# DVCA_v1_3.net
KiCad netlist of a schematic drawn in EAGLE
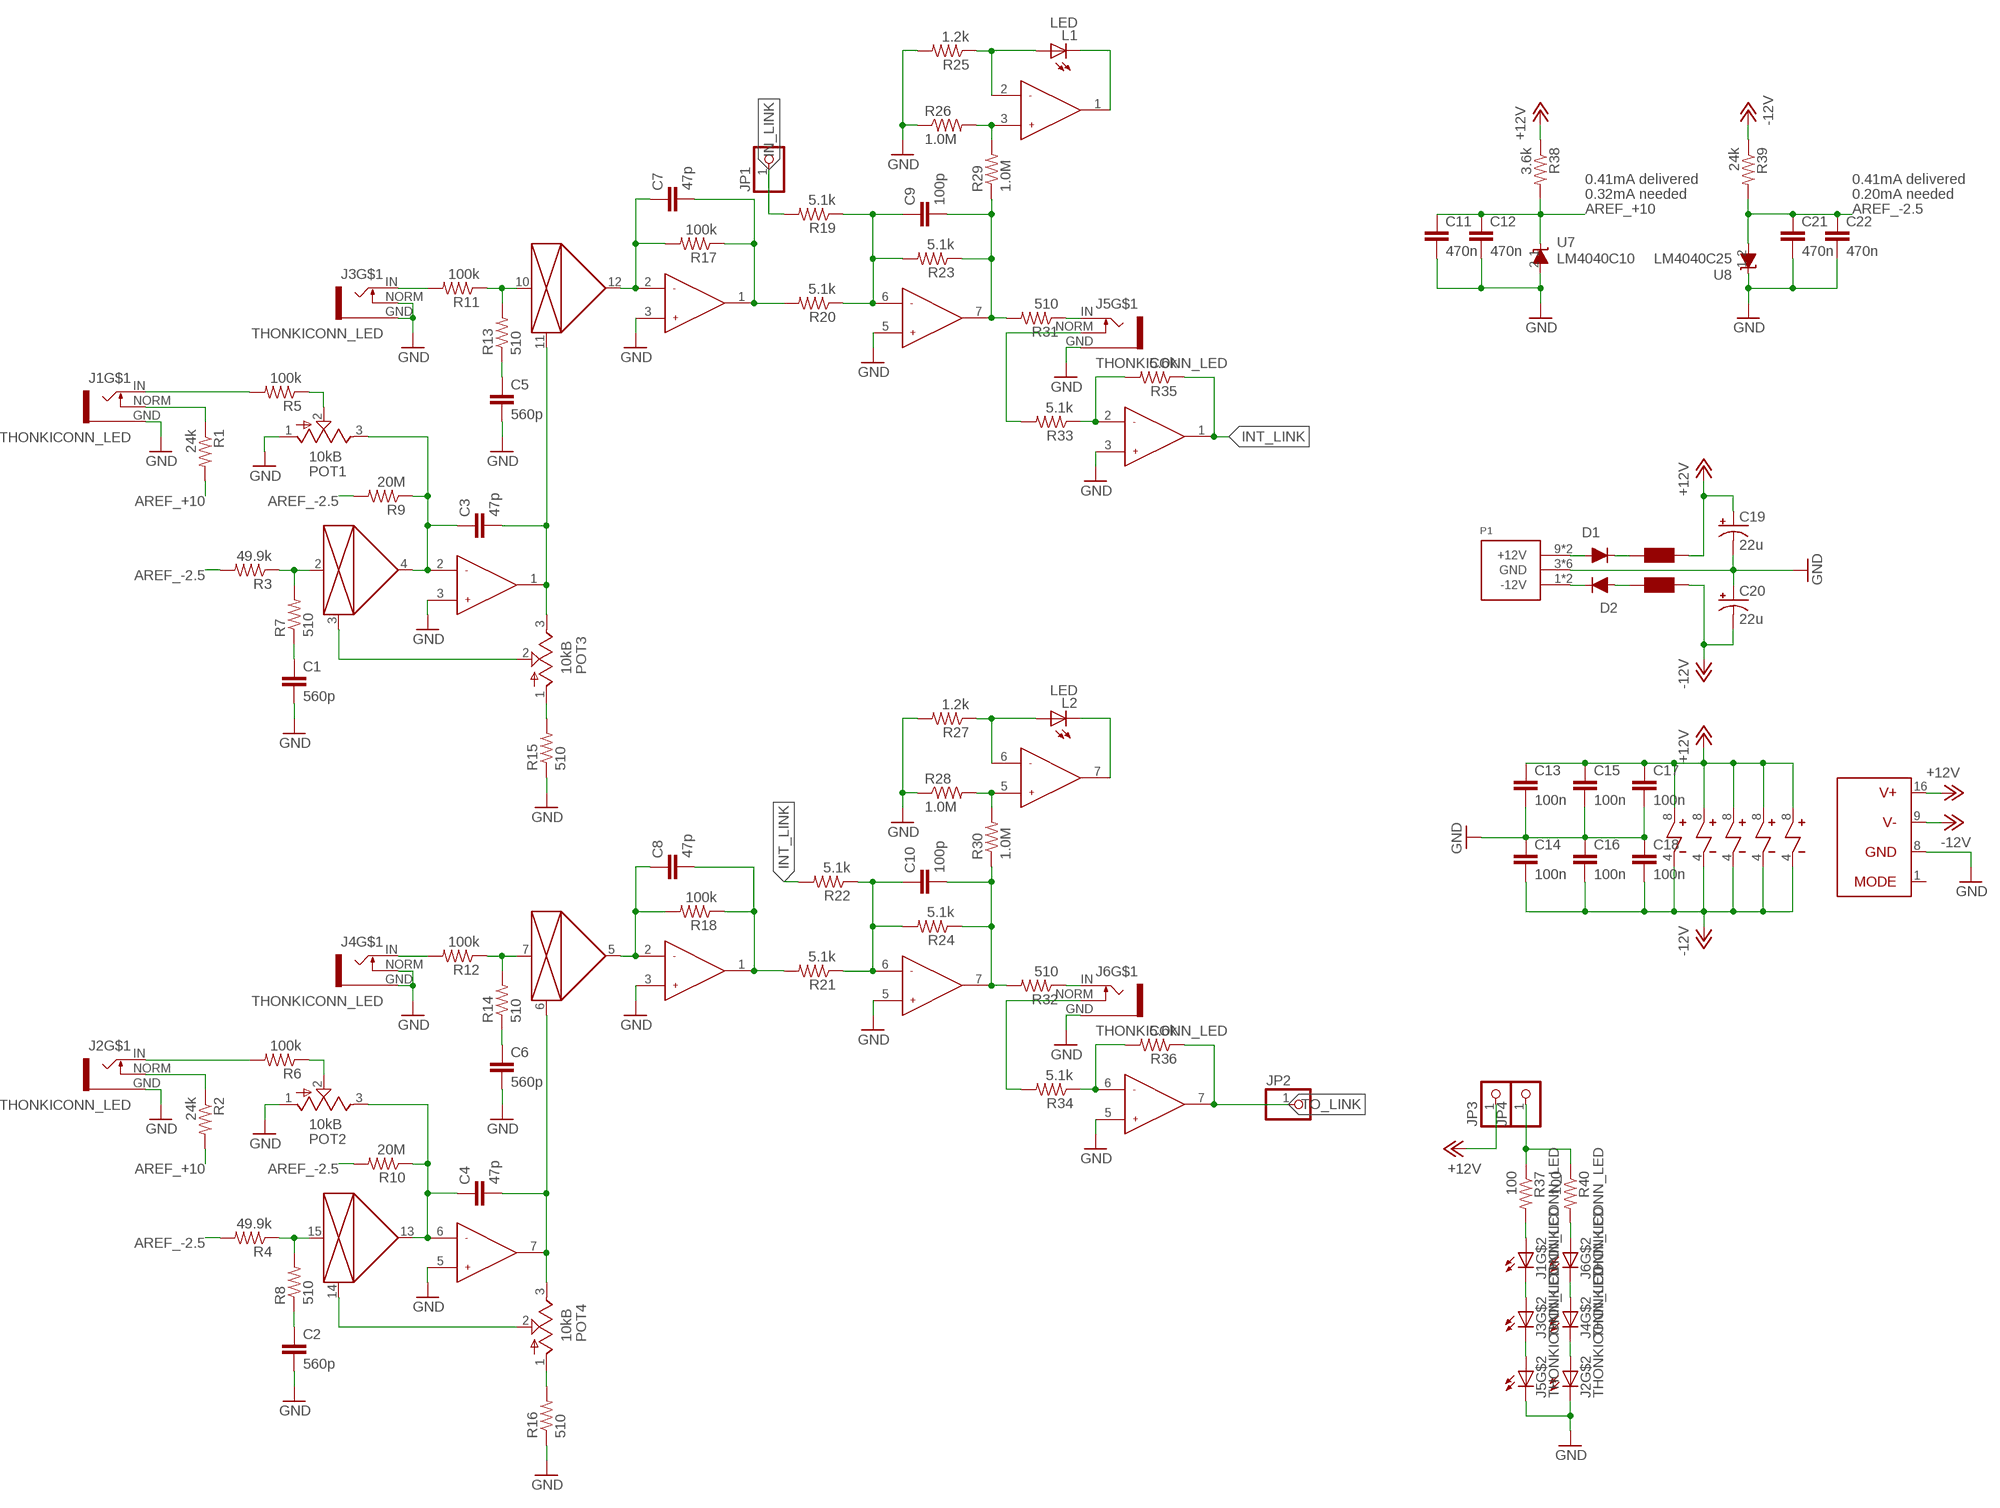
[diagram p0: schematic, sheet 1]

(export (version "E")
  (design (tool "Eeschema 10.0.6"))
  (components
    (comp (ref "C1")
      (value "560p")
      (footprint "eagle-import:RESISTOR_0603")
      (libsource (lib "eagle-import") (part "CAPACITOR"))
    )
    (comp (ref "C2")
      (value "560p")
      (footprint "eagle-import:RESISTOR_0603")
      (libsource (lib "eagle-import") (part "CAPACITOR"))
    )
    (comp (ref "C3")
      (value "47p")
      (footprint "eagle-import:RESISTOR_0603")
      (libsource (lib "eagle-import") (part "CAPACITOR"))
    )
    (comp (ref "C4")
      (value "47p")
      (footprint "eagle-import:RESISTOR_0603")
      (libsource (lib "eagle-import") (part "CAPACITOR"))
    )
    (comp (ref "C5")
      (value "560p")
      (footprint "eagle-import:RESISTOR_0603")
      (libsource (lib "eagle-import") (part "CAPACITOR"))
    )
    (comp (ref "C6")
      (value "560p")
      (footprint "eagle-import:RESISTOR_0603")
      (libsource (lib "eagle-import") (part "CAPACITOR"))
    )
    (comp (ref "C7")
      (value "47p")
      (footprint "eagle-import:RESISTOR_0603")
      (libsource (lib "eagle-import") (part "CAPACITOR"))
    )
    (comp (ref "C8")
      (value "47p")
      (footprint "eagle-import:RESISTOR_0603")
      (libsource (lib "eagle-import") (part "CAPACITOR"))
    )
    (comp (ref "C9")
      (value "100p")
      (footprint "eagle-import:RESISTOR_0603")
      (libsource (lib "eagle-import") (part "CAPACITOR"))
    )
    (comp (ref "C10")
      (value "100p")
      (footprint "eagle-import:RESISTOR_0603")
      (libsource (lib "eagle-import") (part "CAPACITOR"))
    )
    (comp (ref "C11")
      (value "470n")
      (footprint "eagle-import:RESISTOR_0603")
      (libsource (lib "eagle-import") (part "CAPACITOR"))
    )
    (comp (ref "C12")
      (value "470n")
      (footprint "eagle-import:RESISTOR_0603")
      (libsource (lib "eagle-import") (part "CAPACITOR"))
    )
    (comp (ref "C13")
      (value "100n")
      (footprint "eagle-import:RESISTOR_0603")
      (libsource (lib "eagle-import") (part "CAPACITOR"))
    )
    (comp (ref "C14")
      (value "100n")
      (footprint "eagle-import:RESISTOR_0603")
      (libsource (lib "eagle-import") (part "CAPACITOR"))
    )
    (comp (ref "C15")
      (value "100n")
      (footprint "eagle-import:RESISTOR_0603")
      (libsource (lib "eagle-import") (part "CAPACITOR"))
    )
    (comp (ref "C16")
      (value "100n")
      (footprint "eagle-import:RESISTOR_0603")
      (libsource (lib "eagle-import") (part "CAPACITOR"))
    )
    (comp (ref "C17")
      (value "100n")
      (footprint "eagle-import:RESISTOR_0603")
      (libsource (lib "eagle-import") (part "CAPACITOR"))
    )
    (comp (ref "C18")
      (value "100n")
      (footprint "eagle-import:RESISTOR_0603")
      (libsource (lib "eagle-import") (part "CAPACITOR"))
    )
    (comp (ref "C19")
      (value "22u")
      (footprint "eagle-import:PANASONIC_B")
      (libsource (lib "eagle-import") (part "CAP_POL"))
    )
    (comp (ref "C20")
      (value "22u")
      (footprint "eagle-import:PANASONIC_B")
      (libsource (lib "eagle-import") (part "CAP_POL"))
    )
    (comp (ref "C21")
      (value "470n")
      (footprint "eagle-import:RESISTOR_0603")
      (libsource (lib "eagle-import") (part "CAPACITOR"))
    )
    (comp (ref "C22")
      (value "470n")
      (footprint "eagle-import:RESISTOR_0603")
      (libsource (lib "eagle-import") (part "CAPACITOR"))
    )
    (comp (ref "D1")
      (value "1N5819HW")
      (footprint "eagle-import:SOD123")
      (libsource (lib "eagle-import") (part "DIODE"))
    )
    (comp (ref "D2")
      (value "1N5819HW")
      (footprint "eagle-import:SOD123")
      (libsource (lib "eagle-import") (part "DIODE"))
    )
    (comp (ref "F1")
      (value "FERRITE-BEAD")
      (footprint "eagle-import:RESISTOR_0603")
      (libsource (lib "eagle-import") (part "FERRITE-BEAD"))
    )
    (comp (ref "F2")
      (value "FERRITE-BEAD")
      (footprint "eagle-import:RESISTOR_0603")
      (libsource (lib "eagle-import") (part "FERRITE-BEAD"))
    )
    (comp (ref "J1")
      (value "THONKICONN_LED")
      (footprint "eagle-import:LED_JACK")
      (libsource (lib "eagle-import") (part "THONKICONN_LED"))
    )
    (comp (ref "J2")
      (value "THONKICONN_LED")
      (footprint "eagle-import:LED_JACK")
      (libsource (lib "eagle-import") (part "THONKICONN_LED"))
    )
    (comp (ref "J3")
      (value "THONKICONN_LED")
      (footprint "eagle-import:LED_JACK")
      (libsource (lib "eagle-import") (part "THONKICONN_LED"))
    )
    (comp (ref "J4")
      (value "THONKICONN_LED")
      (footprint "eagle-import:LED_JACK")
      (libsource (lib "eagle-import") (part "THONKICONN_LED"))
    )
    (comp (ref "J5")
      (value "THONKICONN_LED")
      (footprint "eagle-import:LED_JACK")
      (libsource (lib "eagle-import") (part "THONKICONN_LED"))
    )
    (comp (ref "J6")
      (value "THONKICONN_LED")
      (footprint "eagle-import:LED_JACK")
      (libsource (lib "eagle-import") (part "THONKICONN_LED"))
    )
    (comp (ref "JP1")
      (value "PINHD-1X1")
      (footprint "eagle-import:1X01")
      (libsource (lib "eagle-import") (part "PINHD-1X1"))
    )
    (comp (ref "JP2")
      (value "PINHD-1X1")
      (footprint "eagle-import:1X01")
      (libsource (lib "eagle-import") (part "PINHD-1X1"))
    )
    (comp (ref "JP3")
      (value "PINHD-1X1")
      (footprint "eagle-import:1X01")
      (libsource (lib "eagle-import") (part "PINHD-1X1"))
    )
    (comp (ref "JP4")
      (value "PINHD-1X1")
      (footprint "eagle-import:1X01")
      (libsource (lib "eagle-import") (part "PINHD-1X1"))
    )
    (comp (ref "L1")
      (value "LED")
      (footprint "eagle-import:LED_3MM")
      (libsource (lib "eagle-import") (part "LED"))
    )
    (comp (ref "L2")
      (value "LED")
      (footprint "eagle-import:LED_3MM")
      (libsource (lib "eagle-import") (part "LED"))
    )
    (comp (ref "P1")
      (value "POWER_SIMPLE10")
      (footprint "eagle-import:POWER_10")
      (libsource (lib "eagle-import") (part "POWER_SIMPLE10"))
    )
    (comp (ref "POT1")
      (value "10kB")
      (footprint "eagle-import:ALPS_POT_VERTICAL")
      (libsource (lib "eagle-import") (part "POT_VERTICAL"))
    )
    (comp (ref "POT2")
      (value "10kB")
      (footprint "eagle-import:ALPS_POT_VERTICAL")
      (libsource (lib "eagle-import") (part "POT_VERTICAL"))
    )
    (comp (ref "POT3")
      (value "10kB")
      (footprint "eagle-import:ALPS_POT_NOHOLE")
      (libsource (lib "eagle-import") (part "POT_VERTICALNOHOLE"))
    )
    (comp (ref "POT4")
      (value "10kB")
      (footprint "eagle-import:ALPS_POT_NOHOLE")
      (libsource (lib "eagle-import") (part "POT_VERTICALNOHOLE"))
    )
    (comp (ref "R1")
      (value "24k")
      (footprint "eagle-import:RESISTOR_0603")
      (libsource (lib "eagle-import") (part "RESISTOR"))
    )
    (comp (ref "R2")
      (value "24k")
      (footprint "eagle-import:RESISTOR_0603")
      (libsource (lib "eagle-import") (part "RESISTOR"))
    )
    (comp (ref "R3")
      (value "49.9k")
      (footprint "eagle-import:RESISTOR_0603")
      (libsource (lib "eagle-import") (part "RESISTOR"))
    )
    (comp (ref "R4")
      (value "49.9k")
      (footprint "eagle-import:RESISTOR_0603")
      (libsource (lib "eagle-import") (part "RESISTOR"))
    )
    (comp (ref "R5")
      (value "100k")
      (footprint "eagle-import:RESISTOR_0603")
      (libsource (lib "eagle-import") (part "RESISTOR"))
    )
    (comp (ref "R6")
      (value "100k")
      (footprint "eagle-import:RESISTOR_0603")
      (libsource (lib "eagle-import") (part "RESISTOR"))
    )
    (comp (ref "R7")
      (value "510")
      (footprint "eagle-import:RESISTOR_0603")
      (libsource (lib "eagle-import") (part "RESISTOR"))
    )
    (comp (ref "R8")
      (value "510")
      (footprint "eagle-import:RESISTOR_0603")
      (libsource (lib "eagle-import") (part "RESISTOR"))
    )
    (comp (ref "R9")
      (value "20M")
      (footprint "eagle-import:RESISTOR_0603")
      (libsource (lib "eagle-import") (part "RESISTOR"))
    )
    (comp (ref "R10")
      (value "20M")
      (footprint "eagle-import:RESISTOR_0603")
      (libsource (lib "eagle-import") (part "RESISTOR"))
    )
    (comp (ref "R11")
      (value "100k")
      (footprint "eagle-import:RESISTOR_0603")
      (libsource (lib "eagle-import") (part "RESISTOR"))
    )
    (comp (ref "R12")
      (value "100k")
      (footprint "eagle-import:RESISTOR_0603")
      (libsource (lib "eagle-import") (part "RESISTOR"))
    )
    (comp (ref "R13")
      (value "510")
      (footprint "eagle-import:RESISTOR_0603")
      (libsource (lib "eagle-import") (part "RESISTOR"))
    )
    (comp (ref "R14")
      (value "510")
      (footprint "eagle-import:RESISTOR_0603")
      (libsource (lib "eagle-import") (part "RESISTOR"))
    )
    (comp (ref "R15")
      (value "510")
      (footprint "eagle-import:RESISTOR_0603")
      (libsource (lib "eagle-import") (part "RESISTOR"))
    )
    (comp (ref "R16")
      (value "510")
      (footprint "eagle-import:RESISTOR_0603")
      (libsource (lib "eagle-import") (part "RESISTOR"))
    )
    (comp (ref "R17")
      (value "100k")
      (footprint "eagle-import:RESISTOR_0603")
      (libsource (lib "eagle-import") (part "RESISTOR"))
    )
    (comp (ref "R18")
      (value "100k")
      (footprint "eagle-import:RESISTOR_0603")
      (libsource (lib "eagle-import") (part "RESISTOR"))
    )
    (comp (ref "R19")
      (value "5.1k")
      (footprint "eagle-import:RESISTOR_0603")
      (libsource (lib "eagle-import") (part "RESISTOR"))
    )
    (comp (ref "R20")
      (value "5.1k")
      (footprint "eagle-import:RESISTOR_0603")
      (libsource (lib "eagle-import") (part "RESISTOR"))
    )
    (comp (ref "R21")
      (value "5.1k")
      (footprint "eagle-import:RESISTOR_0603")
      (libsource (lib "eagle-import") (part "RESISTOR"))
    )
    (comp (ref "R22")
      (value "5.1k")
      (footprint "eagle-import:RESISTOR_0603")
      (libsource (lib "eagle-import") (part "RESISTOR"))
    )
    (comp (ref "R23")
      (value "5.1k")
      (footprint "eagle-import:RESISTOR_0603")
      (libsource (lib "eagle-import") (part "RESISTOR"))
    )
    (comp (ref "R24")
      (value "5.1k")
      (footprint "eagle-import:RESISTOR_0603")
      (libsource (lib "eagle-import") (part "RESISTOR"))
    )
    (comp (ref "R25")
      (value "1.2k")
      (footprint "eagle-import:RESISTOR_0603")
      (libsource (lib "eagle-import") (part "RESISTOR"))
    )
    (comp (ref "R26")
      (value "1.0M")
      (footprint "eagle-import:RESISTOR_0603")
      (libsource (lib "eagle-import") (part "RESISTOR"))
    )
    (comp (ref "R27")
      (value "1.2k")
      (footprint "eagle-import:RESISTOR_0603")
      (libsource (lib "eagle-import") (part "RESISTOR"))
    )
    (comp (ref "R28")
      (value "1.0M")
      (footprint "eagle-import:RESISTOR_0603")
      (libsource (lib "eagle-import") (part "RESISTOR"))
    )
    (comp (ref "R29")
      (value "1.0M")
      (footprint "eagle-import:RESISTOR_0603")
      (libsource (lib "eagle-import") (part "RESISTOR"))
    )
    (comp (ref "R30")
      (value "1.0M")
      (footprint "eagle-import:RESISTOR_0603")
      (libsource (lib "eagle-import") (part "RESISTOR"))
    )
    (comp (ref "R31")
      (value "510")
      (footprint "eagle-import:RESISTOR_0603")
      (libsource (lib "eagle-import") (part "RESISTOR"))
    )
    (comp (ref "R32")
      (value "510")
      (footprint "eagle-import:RESISTOR_0603")
      (libsource (lib "eagle-import") (part "RESISTOR"))
    )
    (comp (ref "R33")
      (value "5.1k")
      (footprint "eagle-import:RESISTOR_0603")
      (libsource (lib "eagle-import") (part "RESISTOR"))
    )
    (comp (ref "R34")
      (value "5.1k")
      (footprint "eagle-import:RESISTOR_0603")
      (libsource (lib "eagle-import") (part "RESISTOR"))
    )
    (comp (ref "R35")
      (value "5.6k")
      (footprint "eagle-import:RESISTOR_0603")
      (libsource (lib "eagle-import") (part "RESISTOR"))
    )
    (comp (ref "R36")
      (value "5.6k")
      (footprint "eagle-import:RESISTOR_0603")
      (libsource (lib "eagle-import") (part "RESISTOR"))
    )
    (comp (ref "R37")
      (value "100")
      (footprint "eagle-import:RESISTOR_0603")
      (libsource (lib "eagle-import") (part "RESISTOR"))
    )
    (comp (ref "R38")
      (value "3.6k")
      (footprint "eagle-import:RESISTOR_0603")
      (libsource (lib "eagle-import") (part "RESISTOR"))
    )
    (comp (ref "R39")
      (value "24k")
      (footprint "eagle-import:RESISTOR_0603")
      (libsource (lib "eagle-import") (part "RESISTOR"))
    )
    (comp (ref "R40")
      (value "100")
      (footprint "eagle-import:RESISTOR_0603")
      (libsource (lib "eagle-import") (part "RESISTOR"))
    )
    (comp (ref "U1")
      (value "V2164M")
      (footprint "eagle-import:SOIC16")
      (libsource (lib "eagle-import") (part "V2164M"))
    )
    (comp (ref "U2")
      (value "OPAMP_DUAL")
      (footprint "eagle-import:SOIC8")
      (libsource (lib "eagle-import") (part "OPAMP_DUAL"))
    )
    (comp (ref "U3")
      (value "OPAMP_DUAL")
      (footprint "eagle-import:SOIC8")
      (libsource (lib "eagle-import") (part "OPAMP_DUAL"))
    )
    (comp (ref "U4")
      (value "OPAMP_DUAL")
      (footprint "eagle-import:SOIC8")
      (libsource (lib "eagle-import") (part "OPAMP_DUAL"))
    )
    (comp (ref "U5")
      (value "OPAMP_DUAL")
      (footprint "eagle-import:SOIC8")
      (libsource (lib "eagle-import") (part "OPAMP_DUAL"))
    )
    (comp (ref "U6")
      (value "OPAMP_DUAL")
      (footprint "eagle-import:SOIC8")
      (libsource (lib "eagle-import") (part "OPAMP_DUAL"))
    )
    (comp (ref "U7")
      (value "LM4040C10")
      (footprint "eagle-import:SOT23")
      (libsource (lib "eagle-import") (part "LM4040SOT23"))
    )
    (comp (ref "U8")
      (value "LM4040C25")
      (footprint "eagle-import:SOT23")
      (libsource (lib "eagle-import") (part "LM4040SOT23"))
    )
  )
  (nets
    (net (code "1") (name "+12V") (class "Default")
      (node (ref "C13") (pin "1") (pinfunction "1_1") (pintype "passive"))
      (node (ref "C15") (pin "1") (pinfunction "1_1") (pintype "passive"))
      (node (ref "C17") (pin "1") (pinfunction "1_1") (pintype "passive"))
      (node (ref "C19") (pin "+") (pinfunction "+_+") (pintype "passive"))
      (node (ref "F1") (pin "1") (pinfunction "P$1_1") (pintype "bidirectional"))
      (node (ref "JP3") (pin "1") (pinfunction "1_1") (pintype "passive"))
      (node (ref "R38") (pin "1") (pinfunction "1_1") (pintype "passive"))
      (node (ref "U1") (pin "16") (pinfunction "P$1_16") (pintype "bidirectional"))
      (node (ref "U2") (pin "8") (pinfunction "P$1_8") (pintype "bidirectional"))
      (node (ref "U3") (pin "8") (pinfunction "P$1_8") (pintype "bidirectional"))
      (node (ref "U4") (pin "8") (pinfunction "P$1_8") (pintype "bidirectional"))
      (node (ref "U5") (pin "8") (pinfunction "P$1_8") (pintype "bidirectional"))
      (node (ref "U6") (pin "8") (pinfunction "P$1_8") (pintype "bidirectional"))
    )
    (net (code "2") (name "-12V") (class "Default")
      (node (ref "C14") (pin "2") (pinfunction "2_2") (pintype "passive"))
      (node (ref "C16") (pin "2") (pinfunction "2_2") (pintype "passive"))
      (node (ref "C18") (pin "2") (pinfunction "2_2") (pintype "passive"))
      (node (ref "C20") (pin "-") (pinfunction "-_-") (pintype "passive"))
      (node (ref "F2") (pin "1") (pinfunction "P$1_1") (pintype "bidirectional"))
      (node (ref "R39") (pin "1") (pinfunction "1_1") (pintype "passive"))
      (node (ref "U1") (pin "9") (pinfunction "P$2_9") (pintype "bidirectional"))
      (node (ref "U2") (pin "4") (pinfunction "P$2_4") (pintype "bidirectional"))
      (node (ref "U3") (pin "4") (pinfunction "P$2_4") (pintype "bidirectional"))
      (node (ref "U4") (pin "4") (pinfunction "P$2_4") (pintype "bidirectional"))
      (node (ref "U5") (pin "4") (pinfunction "P$2_4") (pintype "bidirectional"))
      (node (ref "U6") (pin "4") (pinfunction "P$2_4") (pintype "bidirectional"))
    )
    (net (code "3") (name "/AREF_+10") (class "Default")
      (node (ref "C11") (pin "1") (pinfunction "1_1") (pintype "passive"))
      (node (ref "C12") (pin "1") (pinfunction "1_1") (pintype "passive"))
      (node (ref "R1") (pin "2") (pinfunction "2_2") (pintype "passive"))
      (node (ref "R2") (pin "2") (pinfunction "2_2") (pintype "passive"))
      (node (ref "R38") (pin "2") (pinfunction "2_2") (pintype "passive"))
      (node (ref "U7") (pin "1") (pinfunction "C_1") (pintype "passive"))
    )
    (net (code "4") (name "/AREF_-2.5") (class "Default")
      (node (ref "C21") (pin "1") (pinfunction "1_1") (pintype "passive"))
      (node (ref "C22") (pin "1") (pinfunction "1_1") (pintype "passive"))
      (node (ref "R10") (pin "2") (pinfunction "2_2") (pintype "passive"))
      (node (ref "R3") (pin "2") (pinfunction "2_2") (pintype "passive"))
      (node (ref "R39") (pin "2") (pinfunction "2_2") (pintype "passive"))
      (node (ref "R4") (pin "2") (pinfunction "2_2") (pintype "passive"))
      (node (ref "R9") (pin "2") (pinfunction "2_2") (pintype "passive"))
      (node (ref "U8") (pin "2") (pinfunction "A_2") (pintype "passive"))
    )
    (net (code "5") (name "GND") (class "Default")
      (node (ref "C1") (pin "2") (pinfunction "2_2") (pintype "passive"))
      (node (ref "C11") (pin "2") (pinfunction "2_2") (pintype "passive"))
      (node (ref "C12") (pin "2") (pinfunction "2_2") (pintype "passive"))
      (node (ref "C13") (pin "2") (pinfunction "2_2") (pintype "passive"))
      (node (ref "C14") (pin "1") (pinfunction "1_1") (pintype "passive"))
      (node (ref "C15") (pin "2") (pinfunction "2_2") (pintype "passive"))
      (node (ref "C16") (pin "1") (pinfunction "1_1") (pintype "passive"))
      (node (ref "C17") (pin "2") (pinfunction "2_2") (pintype "passive"))
      (node (ref "C18") (pin "1") (pinfunction "1_1") (pintype "passive"))
      (node (ref "C19") (pin "-") (pinfunction "-_-") (pintype "passive"))
      (node (ref "C2") (pin "2") (pinfunction "2_2") (pintype "passive"))
      (node (ref "C20") (pin "+") (pinfunction "+_+") (pintype "passive"))
      (node (ref "C21") (pin "2") (pinfunction "2_2") (pintype "passive"))
      (node (ref "C22") (pin "2") (pinfunction "2_2") (pintype "passive"))
      (node (ref "C5") (pin "2") (pinfunction "2_2") (pintype "passive"))
      (node (ref "C6") (pin "2") (pinfunction "2_2") (pintype "passive"))
      (node (ref "J1") (pin "GND") (pinfunction "GND_GND") (pintype "passive"))
      (node (ref "J2") (pin "C") (pinfunction "C_C") (pintype "passive"))
      (node (ref "J2") (pin "GND") (pinfunction "GND_GND") (pintype "passive"))
      (node (ref "J3") (pin "GND") (pinfunction "GND_GND") (pintype "passive"))
      (node (ref "J3") (pin "NORM") (pinfunction "NORM_NORM") (pintype "passive"))
      (node (ref "J4") (pin "GND") (pinfunction "GND_GND") (pintype "passive"))
      (node (ref "J4") (pin "NORM") (pinfunction "NORM_NORM") (pintype "passive"))
      (node (ref "J5") (pin "C") (pinfunction "C_C") (pintype "passive"))
      (node (ref "J5") (pin "GND") (pinfunction "GND_GND") (pintype "passive"))
      (node (ref "J6") (pin "GND") (pinfunction "GND_GND") (pintype "passive"))
      (node (ref "P1") (pin "3") (pinfunction "GND_3") (pintype "bidirectional"))
      (node (ref "P1") (pin "4") (pinfunction "GND_4") (pintype "bidirectional"))
      (node (ref "P1") (pin "5") (pinfunction "GND_5") (pintype "bidirectional"))
      (node (ref "P1") (pin "6") (pinfunction "GND_6") (pintype "bidirectional"))
      (node (ref "P1") (pin "7") (pinfunction "GND_7") (pintype "bidirectional"))
      (node (ref "P1") (pin "8") (pinfunction "GND_8") (pintype "bidirectional"))
      (node (ref "POT1") (pin "1") (pinfunction "A_1") (pintype "passive"))
      (node (ref "POT2") (pin "1") (pinfunction "A_1") (pintype "passive"))
      (node (ref "R15") (pin "1") (pinfunction "1_1") (pintype "passive"))
      (node (ref "R16") (pin "1") (pinfunction "1_1") (pintype "passive"))
      (node (ref "R25") (pin "2") (pinfunction "2_2") (pintype "passive"))
      (node (ref "R26") (pin "1") (pinfunction "1_1") (pintype "passive"))
      (node (ref "R27") (pin "2") (pinfunction "2_2") (pintype "passive"))
      (node (ref "R28") (pin "1") (pinfunction "1_1") (pintype "passive"))
      (node (ref "U1") (pin "8") (pinfunction "P$3_8") (pintype "bidirectional"))
      (node (ref "U2") (pin "3") (pinfunction "P$1_3") (pintype "bidirectional"))
      (node (ref "U2") (pin "5") (pinfunction "P$1_5") (pintype "bidirectional"))
      (node (ref "U3") (pin "3") (pinfunction "P$1_3") (pintype "bidirectional"))
      (node (ref "U3") (pin "5") (pinfunction "P$1_5") (pintype "bidirectional"))
      (node (ref "U4") (pin "3") (pinfunction "P$1_3") (pintype "bidirectional"))
      (node (ref "U4") (pin "5") (pinfunction "P$1_5") (pintype "bidirectional"))
      (node (ref "U6") (pin "3") (pinfunction "P$1_3") (pintype "bidirectional"))
      (node (ref "U6") (pin "5") (pinfunction "P$1_5") (pintype "bidirectional"))
      (node (ref "U7") (pin "2") (pinfunction "A_2") (pintype "passive"))
      (node (ref "U8") (pin "1") (pinfunction "C_1") (pintype "passive"))
    )
    (net (code "6") (name "INT_LINK") (class "Default")
      (node (ref "R22") (pin "2") (pinfunction "2_2") (pintype "passive"))
      (node (ref "R35") (pin "1") (pinfunction "1_1") (pintype "passive"))
      (node (ref "U6") (pin "1") (pinfunction "P$3_1") (pintype "bidirectional"))
    )
    (net (code "7") (name "IN_LINK") (class "Default")
      (node (ref "JP1") (pin "1") (pinfunction "1_1") (pintype "passive"))
      (node (ref "R19") (pin "2") (pinfunction "2_2") (pintype "passive"))
    )
    (net (code "8") (name "Net-(C1-Pad1)") (class "Default")
      (node (ref "C1") (pin "1") (pinfunction "1_1") (pintype "passive"))
      (node (ref "R7") (pin "1") (pinfunction "1_1") (pintype "passive"))
    )
    (net (code "9") (name "Net-(C2-Pad1)") (class "Default")
      (node (ref "C2") (pin "1") (pinfunction "1_1") (pintype "passive"))
      (node (ref "R8") (pin "1") (pinfunction "1_1") (pintype "passive"))
    )
    (net (code "10") (name "Net-(C5-Pad1)") (class "Default")
      (node (ref "C5") (pin "1") (pinfunction "1_1") (pintype "passive"))
      (node (ref "R13") (pin "1") (pinfunction "1_1") (pintype "passive"))
    )
    (net (code "11") (name "Net-(C6-Pad1)") (class "Default")
      (node (ref "C6") (pin "1") (pinfunction "1_1") (pintype "passive"))
      (node (ref "R14") (pin "1") (pinfunction "1_1") (pintype "passive"))
    )
    (net (code "12") (name "Net-(D1-Pad+)") (class "Default")
      (node (ref "D1") (pin "+") (pinfunction "+_+") (pintype "passive"))
      (node (ref "P1") (pin "10") (pinfunction "+12V_10") (pintype "bidirectional"))
      (node (ref "P1") (pin "9") (pinfunction "+12V_9") (pintype "bidirectional"))
    )
    (net (code "13") (name "Net-(D2-Pad-)") (class "Default")
      (node (ref "D2") (pin "-") (pinfunction "-_-") (pintype "passive"))
      (node (ref "P1") (pin "1") (pinfunction "-12V_1") (pintype "bidirectional"))
      (node (ref "P1") (pin "2") (pinfunction "-12V_2") (pintype "bidirectional"))
    )
    (net (code "14") (name "Net-(F1-P$2)") (class "Default")
      (node (ref "D1") (pin "-") (pinfunction "-_-") (pintype "passive"))
      (node (ref "F1") (pin "2") (pinfunction "P$2_2") (pintype "bidirectional"))
    )
    (net (code "15") (name "Net-(F2-P$2)") (class "Default")
      (node (ref "D2") (pin "+") (pinfunction "+_+") (pintype "passive"))
      (node (ref "F2") (pin "2") (pinfunction "P$2_2") (pintype "bidirectional"))
    )
    (net (code "16") (name "Net-(J1-PadA)") (class "Default")
      (node (ref "J1") (pin "A") (pinfunction "A_A") (pintype "passive"))
      (node (ref "R37") (pin "2") (pinfunction "2_2") (pintype "passive"))
    )
    (net (code "17") (name "Net-(J1-PadC)") (class "Default")
      (node (ref "J1") (pin "C") (pinfunction "C_C") (pintype "passive"))
      (node (ref "J3") (pin "A") (pinfunction "A_A") (pintype "passive"))
    )
    (net (code "18") (name "Net-(J1-PadIN)") (class "Default")
      (node (ref "J1") (pin "IN") (pinfunction "IN_IN") (pintype "passive"))
      (node (ref "R5") (pin "2") (pinfunction "2_2") (pintype "passive"))
    )
    (net (code "19") (name "Net-(J1-PadNORM)") (class "Default")
      (node (ref "J1") (pin "NORM") (pinfunction "NORM_NORM") (pintype "passive"))
      (node (ref "R1") (pin "1") (pinfunction "1_1") (pintype "passive"))
    )
    (net (code "20") (name "Net-(J2-PadA)") (class "Default")
      (node (ref "J2") (pin "A") (pinfunction "A_A") (pintype "passive"))
      (node (ref "J4") (pin "C") (pinfunction "C_C") (pintype "passive"))
    )
    (net (code "21") (name "Net-(J2-PadIN)") (class "Default")
      (node (ref "J2") (pin "IN") (pinfunction "IN_IN") (pintype "passive"))
      (node (ref "R6") (pin "2") (pinfunction "2_2") (pintype "passive"))
    )
    (net (code "22") (name "Net-(J2-PadNORM)") (class "Default")
      (node (ref "J2") (pin "NORM") (pinfunction "NORM_NORM") (pintype "passive"))
      (node (ref "R2") (pin "1") (pinfunction "1_1") (pintype "passive"))
    )
    (net (code "23") (name "Net-(J3-PadC)") (class "Default")
      (node (ref "J3") (pin "C") (pinfunction "C_C") (pintype "passive"))
      (node (ref "J5") (pin "A") (pinfunction "A_A") (pintype "passive"))
    )
    (net (code "24") (name "Net-(J3-PadIN)") (class "Default")
      (node (ref "J3") (pin "IN") (pinfunction "IN_IN") (pintype "passive"))
      (node (ref "R11") (pin "2") (pinfunction "2_2") (pintype "passive"))
    )
    (net (code "25") (name "Net-(J4-PadA)") (class "Default")
      (node (ref "J4") (pin "A") (pinfunction "A_A") (pintype "passive"))
      (node (ref "J6") (pin "C") (pinfunction "C_C") (pintype "passive"))
    )
    (net (code "26") (name "Net-(J4-PadIN)") (class "Default")
      (node (ref "J4") (pin "IN") (pinfunction "IN_IN") (pintype "passive"))
      (node (ref "R12") (pin "2") (pinfunction "2_2") (pintype "passive"))
    )
    (net (code "27") (name "Net-(J5-PadIN)") (class "Default")
      (node (ref "J5") (pin "IN") (pinfunction "IN_IN") (pintype "passive"))
      (node (ref "R31") (pin "1") (pinfunction "1_1") (pintype "passive"))
    )
    (net (code "28") (name "Net-(J5-PadNORM)") (class "Default")
      (node (ref "J5") (pin "NORM") (pinfunction "NORM_NORM") (pintype "passive"))
      (node (ref "R33") (pin "2") (pinfunction "2_2") (pintype "passive"))
    )
    (net (code "29") (name "Net-(J6-PadA)") (class "Default")
      (node (ref "J6") (pin "A") (pinfunction "A_A") (pintype "passive"))
      (node (ref "R40") (pin "2") (pinfunction "2_2") (pintype "passive"))
    )
    (net (code "30") (name "Net-(J6-PadIN)") (class "Default")
      (node (ref "J6") (pin "IN") (pinfunction "IN_IN") (pintype "passive"))
      (node (ref "R32") (pin "1") (pinfunction "1_1") (pintype "passive"))
    )
    (net (code "31") (name "Net-(J6-PadNORM)") (class "Default")
      (node (ref "J6") (pin "NORM") (pinfunction "NORM_NORM") (pintype "passive"))
      (node (ref "R34") (pin "2") (pinfunction "2_2") (pintype "passive"))
    )
    (net (code "32") (name "Net-(JP4-Pad1)") (class "Default")
      (node (ref "JP4") (pin "1") (pinfunction "1_1") (pintype "passive"))
      (node (ref "R37") (pin "1") (pinfunction "1_1") (pintype "passive"))
      (node (ref "R40") (pin "1") (pinfunction "1_1") (pintype "passive"))
    )
    (net (code "33") (name "Net-(L1-C)") (class "Default")
      (node (ref "L1") (pin "K") (pinfunction "C_K") (pintype "passive"))
      (node (ref "U5") (pin "1") (pinfunction "P$3_1") (pintype "bidirectional"))
    )
    (net (code "34") (name "Net-(L2-C)") (class "Default")
      (node (ref "L2") (pin "K") (pinfunction "C_K") (pintype "passive"))
      (node (ref "U5") (pin "7") (pinfunction "P$3_7") (pintype "bidirectional"))
    )
    (net (code "35") (name "Net-(POT1-B)") (class "Default")
      (node (ref "C3") (pin "1") (pinfunction "1_1") (pintype "passive"))
      (node (ref "POT1") (pin "3") (pinfunction "B_3") (pintype "passive"))
      (node (ref "R9") (pin "1") (pinfunction "1_1") (pintype "passive"))
      (node (ref "U1") (pin "4") (pinfunction "P$3_4") (pintype "bidirectional"))
      (node (ref "U2") (pin "2") (pinfunction "P$2_2") (pintype "bidirectional"))
    )
    (net (code "36") (name "Net-(POT1-W)") (class "Default")
      (node (ref "POT1") (pin "2") (pinfunction "W_2") (pintype "passive"))
      (node (ref "R5") (pin "1") (pinfunction "1_1") (pintype "passive"))
    )
    (net (code "37") (name "Net-(POT2-B)") (class "Default")
      (node (ref "C4") (pin "1") (pinfunction "1_1") (pintype "passive"))
      (node (ref "POT2") (pin "3") (pinfunction "B_3") (pintype "passive"))
      (node (ref "R10") (pin "1") (pinfunction "1_1") (pintype "passive"))
      (node (ref "U1") (pin "13") (pinfunction "P$3_13") (pintype "bidirectional"))
      (node (ref "U2") (pin "6") (pinfunction "P$2_6") (pintype "bidirectional"))
    )
    (net (code "38") (name "Net-(POT2-W)") (class "Default")
      (node (ref "POT2") (pin "2") (pinfunction "W_2") (pintype "passive"))
      (node (ref "R6") (pin "1") (pinfunction "1_1") (pintype "passive"))
    )
    (net (code "39") (name "Net-(POT3-A)") (class "Default")
      (node (ref "POT3") (pin "1") (pinfunction "A_1") (pintype "passive"))
      (node (ref "R15") (pin "2") (pinfunction "2_2") (pintype "passive"))
    )
    (net (code "40") (name "Net-(POT3-B)") (class "Default")
      (node (ref "C3") (pin "2") (pinfunction "2_2") (pintype "passive"))
      (node (ref "POT3") (pin "3") (pinfunction "B_3") (pintype "passive"))
      (node (ref "U1") (pin "11") (pinfunction "P$2_11") (pintype "bidirectional"))
      (node (ref "U2") (pin "1") (pinfunction "P$3_1") (pintype "bidirectional"))
    )
    (net (code "41") (name "Net-(POT3-W)") (class "Default")
      (node (ref "POT3") (pin "2") (pinfunction "W_2") (pintype "passive"))
      (node (ref "U1") (pin "3") (pinfunction "P$2_3") (pintype "bidirectional"))
    )
    (net (code "42") (name "Net-(POT4-A)") (class "Default")
      (node (ref "POT4") (pin "1") (pinfunction "A_1") (pintype "passive"))
      (node (ref "R16") (pin "2") (pinfunction "2_2") (pintype "passive"))
    )
    (net (code "43") (name "Net-(POT4-B)") (class "Default")
      (node (ref "C4") (pin "2") (pinfunction "2_2") (pintype "passive"))
      (node (ref "POT4") (pin "3") (pinfunction "B_3") (pintype "passive"))
      (node (ref "U1") (pin "6") (pinfunction "P$2_6") (pintype "bidirectional"))
      (node (ref "U2") (pin "7") (pinfunction "P$3_7") (pintype "bidirectional"))
    )
    (net (code "44") (name "Net-(POT4-W)") (class "Default")
      (node (ref "POT4") (pin "2") (pinfunction "W_2") (pintype "passive"))
      (node (ref "U1") (pin "14") (pinfunction "P$2_14") (pintype "bidirectional"))
    )
    (net (code "45") (name "Net-(U1A-P$1)") (class "Default")
      (node (ref "R3") (pin "1") (pinfunction "1_1") (pintype "passive"))
      (node (ref "R7") (pin "2") (pinfunction "2_2") (pintype "passive"))
      (node (ref "U1") (pin "2") (pinfunction "P$1_2") (pintype "bidirectional"))
    )
    (net (code "46") (name "Net-(U1B-P$1)") (class "Default")
      (node (ref "R12") (pin "1") (pinfunction "1_1") (pintype "passive"))
      (node (ref "R14") (pin "2") (pinfunction "2_2") (pintype "passive"))
      (node (ref "U1") (pin "7") (pinfunction "P$1_7") (pintype "bidirectional"))
    )
    (net (code "47") (name "Net-(U1B-P$3)") (class "Default")
      (node (ref "C8") (pin "1") (pinfunction "1_1") (pintype "passive"))
      (node (ref "R18") (pin "2") (pinfunction "2_2") (pintype "passive"))
      (node (ref "U1") (pin "5") (pinfunction "P$3_5") (pintype "bidirectional"))
      (node (ref "U4") (pin "2") (pinfunction "P$2_2") (pintype "bidirectional"))
    )
    (net (code "48") (name "Net-(U1C-P$1)") (class "Default")
      (node (ref "R11") (pin "1") (pinfunction "1_1") (pintype "passive"))
      (node (ref "R13") (pin "2") (pinfunction "2_2") (pintype "passive"))
      (node (ref "U1") (pin "10") (pinfunction "P$1_10") (pintype "bidirectional"))
    )
    (net (code "49") (name "Net-(U1C-P$3)") (class "Default")
      (node (ref "C7") (pin "1") (pinfunction "1_1") (pintype "passive"))
      (node (ref "R17") (pin "2") (pinfunction "2_2") (pintype "passive"))
      (node (ref "U1") (pin "12") (pinfunction "P$3_12") (pintype "bidirectional"))
      (node (ref "U3") (pin "2") (pinfunction "P$2_2") (pintype "bidirectional"))
    )
    (net (code "50") (name "Net-(U1D-P$1)") (class "Default")
      (node (ref "R4") (pin "1") (pinfunction "1_1") (pintype "passive"))
      (node (ref "R8") (pin "2") (pinfunction "2_2") (pintype "passive"))
      (node (ref "U1") (pin "15") (pinfunction "P$1_15") (pintype "bidirectional"))
    )
    (net (code "51") (name "Net-(U3A-P$3)") (class "Default")
      (node (ref "C7") (pin "2") (pinfunction "2_2") (pintype "passive"))
      (node (ref "R17") (pin "1") (pinfunction "1_1") (pintype "passive"))
      (node (ref "R20") (pin "2") (pinfunction "2_2") (pintype "passive"))
      (node (ref "U3") (pin "1") (pinfunction "P$3_1") (pintype "bidirectional"))
    )
    (net (code "52") (name "Net-(U3B-P$2)") (class "Default")
      (node (ref "C9") (pin "1") (pinfunction "1_1") (pintype "passive"))
      (node (ref "R19") (pin "1") (pinfunction "1_1") (pintype "passive"))
      (node (ref "R20") (pin "1") (pinfunction "1_1") (pintype "passive"))
      (node (ref "R23") (pin "2") (pinfunction "2_2") (pintype "passive"))
      (node (ref "U3") (pin "6") (pinfunction "P$2_6") (pintype "bidirectional"))
    )
    (net (code "53") (name "Net-(U3B-P$3)") (class "Default")
      (node (ref "C9") (pin "2") (pinfunction "2_2") (pintype "passive"))
      (node (ref "R23") (pin "1") (pinfunction "1_1") (pintype "passive"))
      (node (ref "R29") (pin "1") (pinfunction "1_1") (pintype "passive"))
      (node (ref "R31") (pin "2") (pinfunction "2_2") (pintype "passive"))
      (node (ref "U3") (pin "7") (pinfunction "P$3_7") (pintype "bidirectional"))
    )
    (net (code "54") (name "Net-(U4A-P$3)") (class "Default")
      (node (ref "C8") (pin "2") (pinfunction "2_2") (pintype "passive"))
      (node (ref "R18") (pin "1") (pinfunction "1_1") (pintype "passive"))
      (node (ref "R21") (pin "2") (pinfunction "2_2") (pintype "passive"))
      (node (ref "U4") (pin "1") (pinfunction "P$3_1") (pintype "bidirectional"))
    )
    (net (code "55") (name "Net-(U4B-P$2)") (class "Default")
      (node (ref "C10") (pin "1") (pinfunction "1_1") (pintype "passive"))
      (node (ref "R21") (pin "1") (pinfunction "1_1") (pintype "passive"))
      (node (ref "R22") (pin "1") (pinfunction "1_1") (pintype "passive"))
      (node (ref "R24") (pin "2") (pinfunction "2_2") (pintype "passive"))
      (node (ref "U4") (pin "6") (pinfunction "P$2_6") (pintype "bidirectional"))
    )
    (net (code "56") (name "Net-(U4B-P$3)") (class "Default")
      (node (ref "C10") (pin "2") (pinfunction "2_2") (pintype "passive"))
      (node (ref "R24") (pin "1") (pinfunction "1_1") (pintype "passive"))
      (node (ref "R30") (pin "1") (pinfunction "1_1") (pintype "passive"))
      (node (ref "R32") (pin "2") (pinfunction "2_2") (pintype "passive"))
      (node (ref "U4") (pin "7") (pinfunction "P$3_7") (pintype "bidirectional"))
    )
    (net (code "57") (name "Net-(U5A-P$1)") (class "Default")
      (node (ref "R26") (pin "2") (pinfunction "2_2") (pintype "passive"))
      (node (ref "R29") (pin "2") (pinfunction "2_2") (pintype "passive"))
      (node (ref "U5") (pin "3") (pinfunction "P$1_3") (pintype "bidirectional"))
    )
    (net (code "58") (name "Net-(U5A-P$2)") (class "Default")
      (node (ref "L1") (pin "A") (pinfunction "A_A") (pintype "passive"))
      (node (ref "R25") (pin "1") (pinfunction "1_1") (pintype "passive"))
      (node (ref "U5") (pin "2") (pinfunction "P$2_2") (pintype "bidirectional"))
    )
    (net (code "59") (name "Net-(U5B-P$1)") (class "Default")
      (node (ref "R28") (pin "2") (pinfunction "2_2") (pintype "passive"))
      (node (ref "R30") (pin "2") (pinfunction "2_2") (pintype "passive"))
      (node (ref "U5") (pin "5") (pinfunction "P$1_5") (pintype "bidirectional"))
    )
    (net (code "60") (name "Net-(U5B-P$2)") (class "Default")
      (node (ref "L2") (pin "A") (pinfunction "A_A") (pintype "passive"))
      (node (ref "R27") (pin "1") (pinfunction "1_1") (pintype "passive"))
      (node (ref "U5") (pin "6") (pinfunction "P$2_6") (pintype "bidirectional"))
    )
    (net (code "61") (name "Net-(U6A-P$2)") (class "Default")
      (node (ref "R33") (pin "1") (pinfunction "1_1") (pintype "passive"))
      (node (ref "R35") (pin "2") (pinfunction "2_2") (pintype "passive"))
      (node (ref "U6") (pin "2") (pinfunction "P$2_2") (pintype "bidirectional"))
    )
    (net (code "62") (name "Net-(U6B-P$2)") (class "Default")
      (node (ref "R34") (pin "1") (pinfunction "1_1") (pintype "passive"))
      (node (ref "R36") (pin "2") (pinfunction "2_2") (pintype "passive"))
      (node (ref "U6") (pin "6") (pinfunction "P$2_6") (pintype "bidirectional"))
    )
    (net (code "63") (name "TO_LINK") (class "Default")
      (node (ref "JP2") (pin "1") (pinfunction "1_1") (pintype "passive"))
      (node (ref "R36") (pin "1") (pinfunction "1_1") (pintype "passive"))
      (node (ref "U6") (pin "7") (pinfunction "P$3_7") (pintype "bidirectional"))
    )
    (net (code "64") (name "unconnected-(U1E-P$4-Pad1)") (class "Default")
      (node (ref "U1") (pin "1") (pinfunction "P$4_1") (pintype "bidirectional"))
    )
  )
)
